# BNC-V004.net
KiCad netlist of a schematic drawn in EAGLE
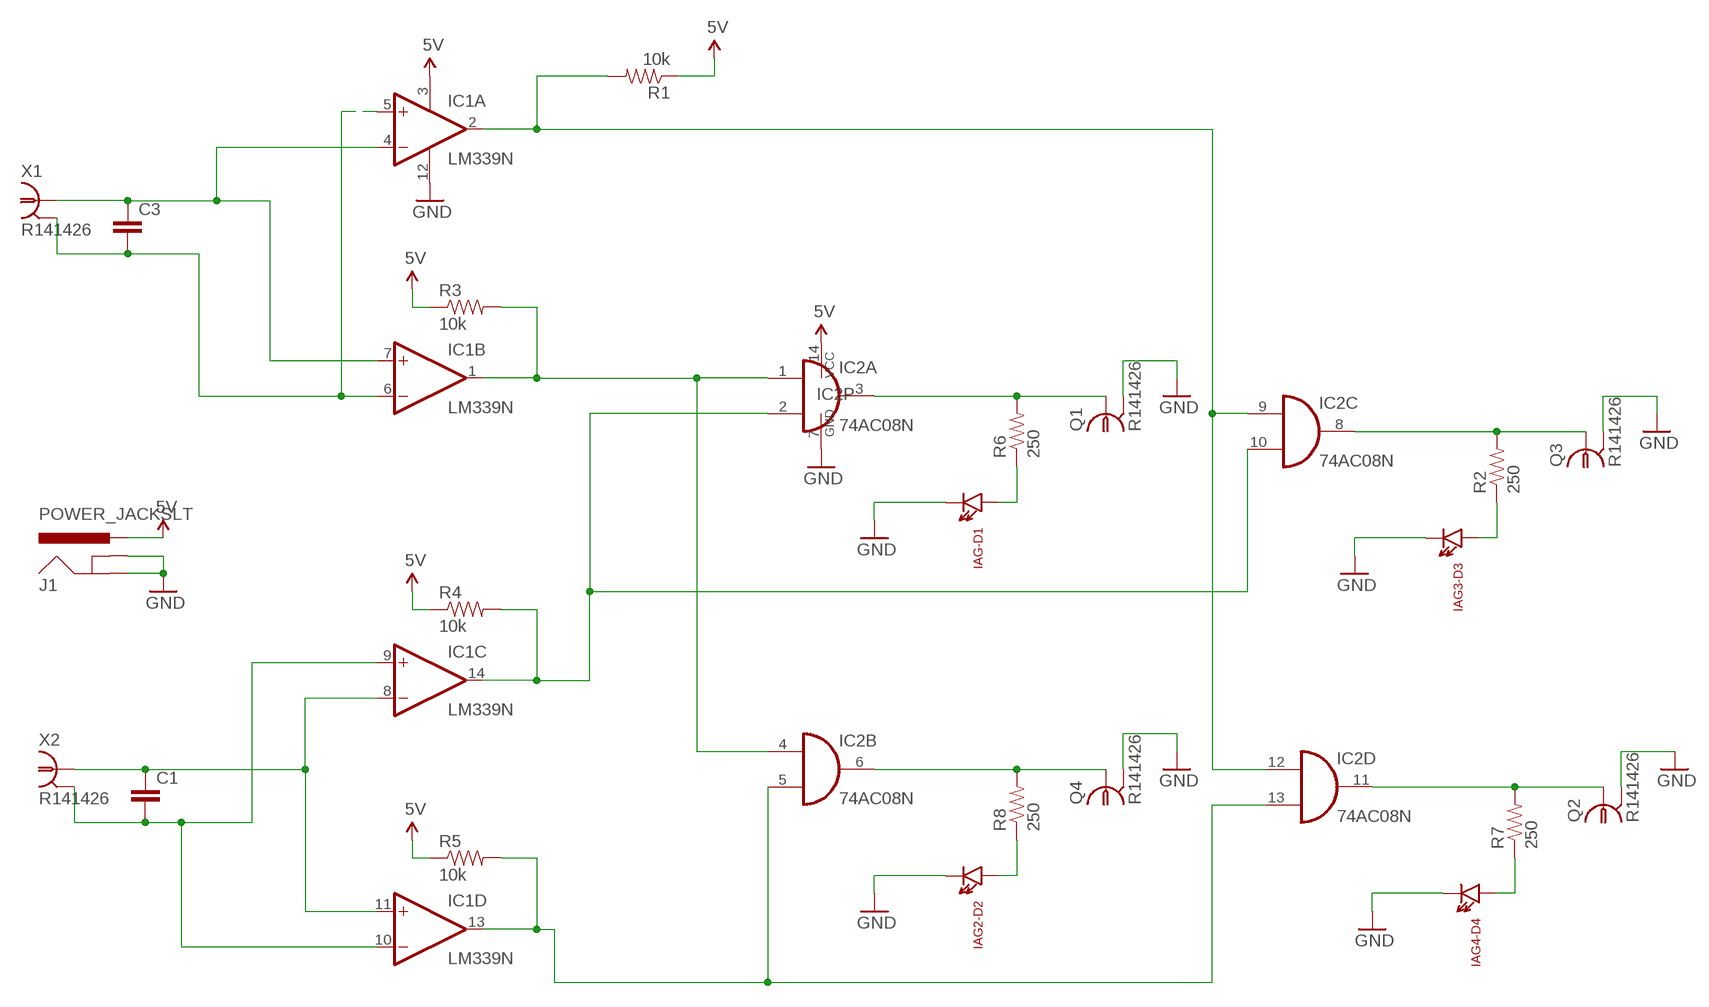
[diagram p0: schematic, sheet 1]

(export (version "E")
  (design (tool "Eeschema 10.0.6"))
  (components
    (comp (ref "C1")
      (value "0.1UF-50V-20%(PTH)KIT-EZ")
      (footprint "eagle-import:CAP-PTH-SMALL-KIT")
      (libsource (lib "eagle-import") (part "0.1UF-50V-20%(PTH)KIT-EZ"))
    )
    (comp (ref "C3")
      (value "0.1UF-50V-20%(PTH)KIT-EZ")
      (footprint "eagle-import:CAP-PTH-SMALL-KIT")
      (libsource (lib "eagle-import") (part "0.1UF-50V-20%(PTH)KIT-EZ"))
    )
    (comp (ref "IAG-D1")
      (value "LTE-302")
      (footprint "eagle-import:LTE-302")
      (libsource (lib "eagle-import") (part "LTE-302"))
    )
    (comp (ref "IAG2-D2")
      (value "LTE-302")
      (footprint "eagle-import:LTE-302")
      (libsource (lib "eagle-import") (part "LTE-302"))
    )
    (comp (ref "IAG3-D3")
      (value "LTE-302")
      (footprint "eagle-import:LTE-302")
      (libsource (lib "eagle-import") (part "LTE-302"))
    )
    (comp (ref "IAG4-D4")
      (value "LTE-302")
      (footprint "eagle-import:LTE-302")
      (libsource (lib "eagle-import") (part "LTE-302"))
    )
    (comp (ref "IC1")
      (value "LM339N")
      (footprint "eagle-import:DIL14")
      (libsource (lib "eagle-import") (part "LM339N"))
    )
    (comp (ref "IC2")
      (value "74AC08N")
      (footprint "eagle-import:DIL14")
      (libsource (lib "eagle-import") (part "7408NAC"))
    )
    (comp (ref "J1")
      (value "POWER_JACKSLT")
      (footprint "eagle-import:POWER_JACK_SLOT")
      (libsource (lib "eagle-import") (part "POWER_JACKSLT"))
    )
    (comp (ref "Q1")
      (value "R141426")
      (footprint "eagle-import:R141426")
      (fields (field (name "MF") "FARNELL") (field (name "MPN") "R141426161"))
      (libsource (lib "eagle-import") (part "R141426"))
    )
    (comp (ref "Q2")
      (value "R141426")
      (footprint "eagle-import:R141426")
      (fields (field (name "MF") "FARNELL") (field (name "MPN") "R141426161"))
      (libsource (lib "eagle-import") (part "R141426"))
    )
    (comp (ref "Q3")
      (value "R141426")
      (footprint "eagle-import:R141426")
      (fields (field (name "MF") "FARNELL") (field (name "MPN") "R141426161"))
      (libsource (lib "eagle-import") (part "R141426"))
    )
    (comp (ref "Q4")
      (value "R141426")
      (footprint "eagle-import:R141426")
      (fields (field (name "MF") "FARNELL") (field (name "MPN") "R141426161"))
      (libsource (lib "eagle-import") (part "R141426"))
    )
    (comp (ref "R1")
      (value "10k")
      (footprint "eagle-import:AXIAL-0.3")
      (libsource (lib "eagle-import") (part "10KOHM-1/4W-1%(PTH)HORIZ"))
    )
    (comp (ref "R2")
      (value "250")
      (footprint "eagle-import:AXIAL-0.3")
      (libsource (lib "eagle-import") (part "1KOHM-1/4W-1%(PTH)"))
    )
    (comp (ref "R3")
      (value "10k")
      (footprint "eagle-import:AXIAL-0.3")
      (libsource (lib "eagle-import") (part "10KOHM-1/4W-1%(PTH)HORIZ"))
    )
    (comp (ref "R4")
      (value "10k")
      (footprint "eagle-import:AXIAL-0.3")
      (libsource (lib "eagle-import") (part "10KOHM-1/4W-1%(PTH)HORIZ"))
    )
    (comp (ref "R5")
      (value "10k")
      (footprint "eagle-import:AXIAL-0.3")
      (libsource (lib "eagle-import") (part "10KOHM-1/4W-1%(PTH)HORIZ"))
    )
    (comp (ref "R6")
      (value "250")
      (footprint "eagle-import:AXIAL-0.3")
      (libsource (lib "eagle-import") (part "1KOHM-1/4W-1%(PTH)"))
    )
    (comp (ref "R7")
      (value "250")
      (footprint "eagle-import:AXIAL-0.3")
      (libsource (lib "eagle-import") (part "1KOHM-1/4W-1%(PTH)"))
    )
    (comp (ref "R8")
      (value "250")
      (footprint "eagle-import:AXIAL-0.3")
      (libsource (lib "eagle-import") (part "1KOHM-1/4W-1%(PTH)"))
    )
    (comp (ref "X1")
      (value "R141426")
      (footprint "eagle-import:R141426")
      (fields (field (name "MF") "FARNELL") (field (name "MPN") "R141426161"))
      (libsource (lib "eagle-import") (part "R141426"))
    )
    (comp (ref "X2")
      (value "R141426")
      (footprint "eagle-import:R141426")
      (fields (field (name "MF") "FARNELL") (field (name "MPN") "R141426161"))
      (libsource (lib "eagle-import") (part "R141426"))
    )
  )
  (nets
    (net (code "1") (name "5V") (class "Default")
      (node (ref "IC1") (pin "3") (pinfunction "V+_3") (pintype "power_in"))
      (node (ref "IC2") (pin "14") (pinfunction "VCC_14") (pintype "power_in"))
      (node (ref "J1") (pin "PWR") (pinfunction "PWR_PWR") (pintype "bidirectional"))
      (node (ref "R1") (pin "P$1") (pinfunction "1_P$1") (pintype "passive"))
      (node (ref "R3") (pin "P$1") (pinfunction "1_P$1") (pintype "passive"))
      (node (ref "R4") (pin "P$1") (pinfunction "1_P$1") (pintype "passive"))
      (node (ref "R5") (pin "P$1") (pinfunction "1_P$1") (pintype "passive"))
    )
    (net (code "2") (name "GND") (class "Default")
      (node (ref "IAG-D1") (pin "C") (pinfunction "C_C") (pintype "bidirectional"))
      (node (ref "IAG2-D2") (pin "C") (pinfunction "C_C") (pintype "bidirectional"))
      (node (ref "IAG3-D3") (pin "C") (pinfunction "C_C") (pintype "bidirectional"))
      (node (ref "IAG4-D4") (pin "C") (pinfunction "C_C") (pintype "bidirectional"))
      (node (ref "IC1") (pin "12") (pinfunction "GND_12") (pintype "power_in"))
      (node (ref "IC2") (pin "7") (pinfunction "GND_7") (pintype "power_in"))
      (node (ref "J1") (pin "GND@1") (pinfunction "GNDBREAK_GND@1") (pintype "bidirectional"))
      (node (ref "J1") (pin "GND@2") (pinfunction "GND_GND@2") (pintype "bidirectional"))
      (node (ref "Q1") (pin "2") (pinfunction "2_2") (pintype "passive"))
      (node (ref "Q1") (pin "3") (pinfunction "2_3") (pintype "passive"))
      (node (ref "Q1") (pin "4") (pinfunction "2_4") (pintype "passive"))
      (node (ref "Q1") (pin "5") (pinfunction "2_5") (pintype "passive"))
      (node (ref "Q2") (pin "2") (pinfunction "2_2") (pintype "passive"))
      (node (ref "Q2") (pin "3") (pinfunction "2_3") (pintype "passive"))
      (node (ref "Q2") (pin "4") (pinfunction "2_4") (pintype "passive"))
      (node (ref "Q2") (pin "5") (pinfunction "2_5") (pintype "passive"))
      (node (ref "Q3") (pin "2") (pinfunction "2_2") (pintype "passive"))
      (node (ref "Q3") (pin "3") (pinfunction "2_3") (pintype "passive"))
      (node (ref "Q3") (pin "4") (pinfunction "2_4") (pintype "passive"))
      (node (ref "Q3") (pin "5") (pinfunction "2_5") (pintype "passive"))
      (node (ref "Q4") (pin "2") (pinfunction "2_2") (pintype "passive"))
      (node (ref "Q4") (pin "3") (pinfunction "2_3") (pintype "passive"))
      (node (ref "Q4") (pin "4") (pinfunction "2_4") (pintype "passive"))
      (node (ref "Q4") (pin "5") (pinfunction "2_5") (pintype "passive"))
    )
    (net (code "3") (name "Net-(IC1A-+IN)") (class "Default")
      (node (ref "C3") (pin "2") (pinfunction "2_2") (pintype "passive"))
      (node (ref "IC1") (pin "5") (pinfunction "+IN_5") (pintype "input"))
      (node (ref "IC1") (pin "6") (pinfunction "-IN_6") (pintype "input"))
      (node (ref "X1") (pin "2") (pinfunction "2_2") (pintype "passive"))
      (node (ref "X1") (pin "3") (pinfunction "2_3") (pintype "passive"))
      (node (ref "X1") (pin "4") (pinfunction "2_4") (pintype "passive"))
      (node (ref "X1") (pin "5") (pinfunction "2_5") (pintype "passive"))
    )
    (net (code "4") (name "Net-(IC1A--IN)") (class "Default")
      (node (ref "C3") (pin "1") (pinfunction "1_1") (pintype "passive"))
      (node (ref "IC1") (pin "4") (pinfunction "-IN_4") (pintype "input"))
      (node (ref "IC1") (pin "7") (pinfunction "+IN_7") (pintype "input"))
      (node (ref "X1") (pin "1") (pinfunction "1_1") (pintype "passive"))
    )
    (net (code "5") (name "Net-(IC1A-OUT)") (class "Default")
      (node (ref "IC1") (pin "2") (pinfunction "OUT_2") (pintype "open_collector"))
      (node (ref "IC2") (pin "12") (pinfunction "I0_12") (pintype "input"))
      (node (ref "IC2") (pin "9") (pinfunction "I0_9") (pintype "input"))
      (node (ref "R1") (pin "P$2") (pinfunction "2_P$2") (pintype "passive"))
    )
    (net (code "6") (name "Net-(IC1B-OUT)") (class "Default")
      (node (ref "IC1") (pin "1") (pinfunction "OUT_1") (pintype "open_collector"))
      (node (ref "IC2") (pin "1") (pinfunction "I0_1") (pintype "input"))
      (node (ref "IC2") (pin "4") (pinfunction "I0_4") (pintype "input"))
      (node (ref "R3") (pin "P$2") (pinfunction "2_P$2") (pintype "passive"))
    )
    (net (code "7") (name "Net-(IC1C-+IN)") (class "Default")
      (node (ref "C1") (pin "2") (pinfunction "2_2") (pintype "passive"))
      (node (ref "IC1") (pin "10") (pinfunction "-IN_10") (pintype "input"))
      (node (ref "IC1") (pin "9") (pinfunction "+IN_9") (pintype "input"))
      (node (ref "X2") (pin "2") (pinfunction "2_2") (pintype "passive"))
      (node (ref "X2") (pin "3") (pinfunction "2_3") (pintype "passive"))
      (node (ref "X2") (pin "4") (pinfunction "2_4") (pintype "passive"))
      (node (ref "X2") (pin "5") (pinfunction "2_5") (pintype "passive"))
    )
    (net (code "8") (name "Net-(IC1C--IN)") (class "Default")
      (node (ref "C1") (pin "1") (pinfunction "1_1") (pintype "passive"))
      (node (ref "IC1") (pin "11") (pinfunction "+IN_11") (pintype "input"))
      (node (ref "IC1") (pin "8") (pinfunction "-IN_8") (pintype "input"))
      (node (ref "X2") (pin "1") (pinfunction "1_1") (pintype "passive"))
    )
    (net (code "9") (name "Net-(IC1C-OUT)") (class "Default")
      (node (ref "IC1") (pin "14") (pinfunction "OUT_14") (pintype "open_collector"))
      (node (ref "IC2") (pin "10") (pinfunction "I1_10") (pintype "input"))
      (node (ref "IC2") (pin "2") (pinfunction "I1_2") (pintype "input"))
      (node (ref "R4") (pin "P$2") (pinfunction "2_P$2") (pintype "passive"))
    )
    (net (code "10") (name "Net-(IC1D-OUT)") (class "Default")
      (node (ref "IC1") (pin "13") (pinfunction "OUT_13") (pintype "open_collector"))
      (node (ref "IC2") (pin "13") (pinfunction "I1_13") (pintype "input"))
      (node (ref "IC2") (pin "5") (pinfunction "I1_5") (pintype "input"))
      (node (ref "R5") (pin "P$2") (pinfunction "2_P$2") (pintype "passive"))
    )
    (net (code "11") (name "Net-(IC2A-O)") (class "Default")
      (node (ref "IC2") (pin "3") (pinfunction "O_3") (pintype "output"))
      (node (ref "Q1") (pin "1") (pinfunction "1_1") (pintype "passive"))
      (node (ref "R6") (pin "P$2") (pinfunction "2_P$2") (pintype "passive"))
    )
    (net (code "12") (name "Net-(IC2B-O)") (class "Default")
      (node (ref "IC2") (pin "6") (pinfunction "O_6") (pintype "output"))
      (node (ref "Q4") (pin "1") (pinfunction "1_1") (pintype "passive"))
      (node (ref "R8") (pin "P$2") (pinfunction "2_P$2") (pintype "passive"))
    )
    (net (code "13") (name "Net-(IC2C-O)") (class "Default")
      (node (ref "IC2") (pin "8") (pinfunction "O_8") (pintype "output"))
      (node (ref "Q3") (pin "1") (pinfunction "1_1") (pintype "passive"))
      (node (ref "R2") (pin "P$2") (pinfunction "2_P$2") (pintype "passive"))
    )
    (net (code "14") (name "Net-(IC2D-O)") (class "Default")
      (node (ref "IC2") (pin "11") (pinfunction "O_11") (pintype "output"))
      (node (ref "Q2") (pin "1") (pinfunction "1_1") (pintype "passive"))
      (node (ref "R7") (pin "P$2") (pinfunction "2_P$2") (pintype "passive"))
    )
    (net (code "15") (name "Net-(R2-1)") (class "Default")
      (node (ref "IAG3-D3") (pin "A") (pinfunction "A_A") (pintype "bidirectional"))
      (node (ref "R2") (pin "P$1") (pinfunction "1_P$1") (pintype "passive"))
    )
    (net (code "16") (name "Net-(R6-1)") (class "Default")
      (node (ref "IAG-D1") (pin "A") (pinfunction "A_A") (pintype "bidirectional"))
      (node (ref "R6") (pin "P$1") (pinfunction "1_P$1") (pintype "passive"))
    )
    (net (code "17") (name "Net-(R7-1)") (class "Default")
      (node (ref "IAG4-D4") (pin "A") (pinfunction "A_A") (pintype "bidirectional"))
      (node (ref "R7") (pin "P$1") (pinfunction "1_P$1") (pintype "passive"))
    )
    (net (code "18") (name "Net-(R8-1)") (class "Default")
      (node (ref "IAG2-D2") (pin "A") (pinfunction "A_A") (pintype "bidirectional"))
      (node (ref "R8") (pin "P$1") (pinfunction "1_P$1") (pintype "passive"))
    )
  )
)
